# Holoboard_mezzanine.net
KiCad netlist of a schematic drawn in Altium Designer
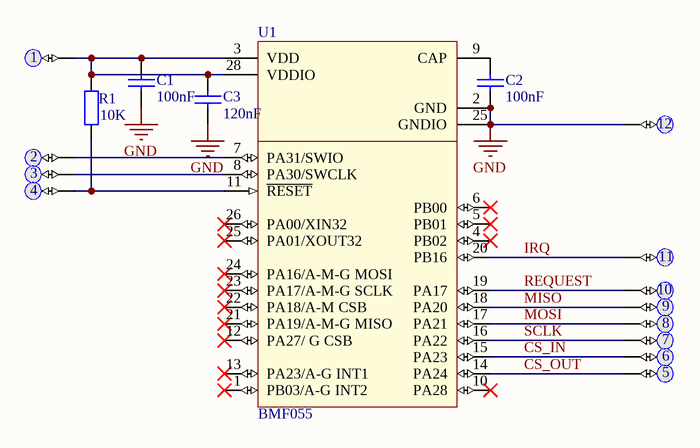
[diagram p0: Holoboard_mezzanine.SchDoc]

(export (version "E")
  (design (tool "Eeschema 10.0.6"))
  (components
    (comp (ref "1") (value "Pad") (footprint "PAD") (libsource (lib "LIBRARY IGREBOT") (part "Pad")))
    (comp (ref "2") (value "Pad") (footprint "PAD") (libsource (lib "LIBRARY IGREBOT") (part "Pad")))
    (comp (ref "3") (value "Pad") (footprint "PAD") (libsource (lib "LIBRARY IGREBOT") (part "Pad")))
    (comp (ref "4") (value "Pad") (footprint "PAD") (libsource (lib "LIBRARY IGREBOT") (part "Pad")))
    (comp (ref "5") (value "Pad") (footprint "PAD") (libsource (lib "LIBRARY IGREBOT") (part "Pad")))
    (comp (ref "6") (value "Pad") (footprint "PAD") (libsource (lib "LIBRARY IGREBOT") (part "Pad")))
    (comp (ref "7") (value "Pad") (footprint "PAD") (libsource (lib "LIBRARY IGREBOT") (part "Pad")))
    (comp (ref "8") (value "Pad") (footprint "PAD") (libsource (lib "LIBRARY IGREBOT") (part "Pad")))
    (comp (ref "9") (value "Pad") (footprint "PAD") (libsource (lib "LIBRARY IGREBOT") (part "Pad")))
    (comp (ref "10") (value "Pad") (footprint "PAD") (libsource (lib "LIBRARY IGREBOT") (part "Pad")))
    (comp (ref "11") (value "Pad") (footprint "PAD") (libsource (lib "LIBRARY IGREBOT") (part "Pad")))
    (comp (ref "12") (value "Pad") (footprint "PAD") (libsource (lib "LIBRARY IGREBOT") (part "Pad")))
    (comp (ref "C1")
      (value "100nF")
      (footprint "C0402")
      (description "Capacitor")
      (fields (field (name "Comment") "Cap") (field (name "PUBLISHER") "Altium Limited"))
      (libsource (lib "LIBRARY IGREBOT") (part "Cap"))
    )
    (comp (ref "C2")
      (value "100nF")
      (footprint "C0402")
      (description "Capacitor")
      (fields (field (name "Comment") "Cap") (field (name "PUBLISHER") "Altium Limited"))
      (libsource (lib "LIBRARY IGREBOT") (part "Cap"))
    )
    (comp (ref "C3")
      (value "120nF")
      (footprint "C0402")
      (description "Capacitor")
      (fields (field (name "Comment") "Cap") (field (name "PUBLISHER") "Altium Limited"))
      (libsource (lib "LIBRARY IGREBOT") (part "Cap"))
    )
    (comp (ref "R1")
      (value "10K")
      (footprint "0402")
      (description "Resistor")
      (fields (field (name "Comment") "Res2") (field (name "PUBLISHER") "Altium Limited"))
      (libsource (lib "LIBRARY IGREBOT") (part "Res2"))
    )
    (comp (ref "U1") (value "BMF055") (footprint "LGA28") (libsource (lib "LIBRARY IGREBOT") (part "BMF055")))
  )
  (nets
    (net (code "1") (name "/CS_IN") (class "Default")
      (node (ref "6") (pin "1") (pinfunction "Pad_1") (pintype "bidirectional"))
      (node (ref "U1") (pin "15") (pinfunction "PA23_15") (pintype "bidirectional"))
    )
    (net (code "2") (name "/CS_OUT") (class "Default")
      (node (ref "5") (pin "1") (pinfunction "Pad_1") (pintype "bidirectional"))
      (node (ref "U1") (pin "14") (pinfunction "PA24_14") (pintype "bidirectional"))
    )
    (net (code "3") (name "/IRQ") (class "Default")
      (node (ref "11") (pin "1") (pinfunction "Pad_1") (pintype "bidirectional"))
      (node (ref "U1") (pin "20") (pinfunction "PB16_20") (pintype "bidirectional"))
    )
    (net (code "4") (name "/MISO") (class "Default")
      (node (ref "9") (pin "1") (pinfunction "Pad_1") (pintype "bidirectional"))
      (node (ref "U1") (pin "18") (pinfunction "PA20_18") (pintype "bidirectional"))
    )
    (net (code "5") (name "/MOSI") (class "Default")
      (node (ref "8") (pin "1") (pinfunction "Pad_1") (pintype "bidirectional"))
      (node (ref "U1") (pin "17") (pinfunction "PA21_17") (pintype "bidirectional"))
    )
    (net (code "6") (name "/REQUEST") (class "Default")
      (node (ref "10") (pin "1") (pinfunction "Pad_1") (pintype "bidirectional"))
      (node (ref "U1") (pin "19") (pinfunction "PA17_19") (pintype "bidirectional"))
    )
    (net (code "7") (name "/SCLK") (class "Default")
      (node (ref "7") (pin "1") (pinfunction "Pad_1") (pintype "bidirectional"))
      (node (ref "U1") (pin "16") (pinfunction "PA22_16") (pintype "bidirectional"))
    )
    (net (code "8") (name "GND") (class "Default")
      (node (ref "12") (pin "1") (pinfunction "Pad_1") (pintype "bidirectional"))
      (node (ref "C1") (pin "2") (pinfunction "2_2") (pintype "passive"))
      (node (ref "C2") (pin "1") (pinfunction "1_1") (pintype "passive"))
      (node (ref "C3") (pin "1") (pinfunction "1_1") (pintype "passive"))
      (node (ref "U1") (pin "2") (pinfunction "GND_2") (pintype "power_in"))
      (node (ref "U1") (pin "25") (pinfunction "GNDIO_25") (pintype "power_in"))
    )
    (net (code "9") (name "Net-(U1-CAP)") (class "Default")
      (node (ref "C2") (pin "2") (pinfunction "2_2") (pintype "passive"))
      (node (ref "U1") (pin "9") (pinfunction "CAP_9") (pintype "passive"))
    )
    (net (code "10") (name "Net-(U1-PA30{slash}SWCLK)") (class "Default")
      (node (ref "3") (pin "1") (pinfunction "Pad_1") (pintype "bidirectional"))
      (node (ref "U1") (pin "8") (pinfunction "PA30/SWCLK_8") (pintype "bidirectional"))
    )
    (net (code "11") (name "Net-(U1-PA31{slash}SWIO)") (class "Default")
      (node (ref "2") (pin "1") (pinfunction "Pad_1") (pintype "bidirectional"))
      (node (ref "U1") (pin "7") (pinfunction "PA31/SWIO_7") (pintype "bidirectional"))
    )
    (net (code "12") (name "Net-(U1-VDD)") (class "Default")
      (node (ref "1") (pin "1") (pinfunction "Pad_1") (pintype "bidirectional"))
      (node (ref "C1") (pin "1") (pinfunction "1_1") (pintype "passive"))
      (node (ref "C3") (pin "2") (pinfunction "2_2") (pintype "passive"))
      (node (ref "R1") (pin "2") (pinfunction "2_2") (pintype "passive"))
      (node (ref "U1") (pin "28") (pinfunction "VDDIO_28") (pintype "power_in"))
      (node (ref "U1") (pin "3") (pinfunction "VDD_3") (pintype "power_in"))
    )
    (net (code "13") (name "Net-(U1-~{RESET})") (class "Default")
      (node (ref "4") (pin "1") (pinfunction "Pad_1") (pintype "bidirectional"))
      (node (ref "R1") (pin "1") (pinfunction "1_1") (pintype "passive"))
      (node (ref "U1") (pin "11") (pinfunction "~{RESET}_11") (pintype "input"))
    )
    (net (code "14") (name "unconnected-(U1-PA00{slash}XIN32-Pad26)") (class "Default")
      (node (ref "U1") (pin "26") (pinfunction "PA00/XIN32_26") (pintype "bidirectional+no_connect"))
    )
    (net (code "15") (name "unconnected-(U1-PA01{slash}XOUT32-Pad25)") (class "Default")
      (node (ref "U1") (pin "25") (pinfunction "PA01/XOUT32_25") (pintype "bidirectional+no_connect"))
    )
    (net (code "16") (name "unconnected-(U1-PA16{slash}A-M-G_MOSI-Pad24)") (class "Default")
      (node (ref "U1") (pin "24") (pinfunction "PA16/A-M-G_MOSI_24") (pintype "bidirectional+no_connect"))
    )
    (net (code "17") (name "unconnected-(U1-PA17{slash}A-M-G_SCLK-Pad23)") (class "Default")
      (node (ref "U1") (pin "23") (pinfunction "PA17/A-M-G_SCLK_23") (pintype "bidirectional+no_connect"))
    )
    (net (code "18") (name "unconnected-(U1-PA18{slash}A-M_CSB-Pad22)") (class "Default")
      (node (ref "U1") (pin "22") (pinfunction "PA18/A-M_CSB_22") (pintype "bidirectional+no_connect"))
    )
    (net (code "19") (name "unconnected-(U1-PA19{slash}A-M-G_MISO-Pad21)") (class "Default")
      (node (ref "U1") (pin "21") (pinfunction "PA19/A-M-G_MISO_21") (pintype "bidirectional+no_connect"))
    )
    (net (code "20") (name "unconnected-(U1-PA23{slash}A-G_INT1-Pad13)") (class "Default")
      (node (ref "U1") (pin "13") (pinfunction "PA23/A-G_INT1_13") (pintype "bidirectional+no_connect"))
    )
    (net (code "21") (name "unconnected-(U1-PA27{slash}_G_CSB-Pad12)") (class "Default")
      (node (ref "U1") (pin "12") (pinfunction "PA27/_G_CSB_12") (pintype "bidirectional+no_connect"))
    )
    (net (code "22") (name "unconnected-(U1-PA28-Pad10)") (class "Default")
      (node (ref "U1") (pin "10") (pinfunction "PA28_10") (pintype "bidirectional+no_connect"))
    )
    (net (code "23") (name "unconnected-(U1-PB00-Pad6)") (class "Default")
      (node (ref "U1") (pin "6") (pinfunction "PB00_6") (pintype "bidirectional+no_connect"))
    )
    (net (code "24") (name "unconnected-(U1-PB01-Pad5)") (class "Default")
      (node (ref "U1") (pin "5") (pinfunction "PB01_5") (pintype "bidirectional+no_connect"))
    )
    (net (code "25") (name "unconnected-(U1-PB02-Pad4)") (class "Default")
      (node (ref "U1") (pin "4") (pinfunction "PB02_4") (pintype "bidirectional+no_connect"))
    )
    (net (code "26") (name "unconnected-(U1-PB03{slash}A-G_INT2-Pad1)") (class "Default")
      (node (ref "U1") (pin "1") (pinfunction "PB03/A-G_INT2_1") (pintype "bidirectional+no_connect"))
    )
  )
)
